# Microcontroller.net
KiCad netlist of a schematic drawn in Altium Designer
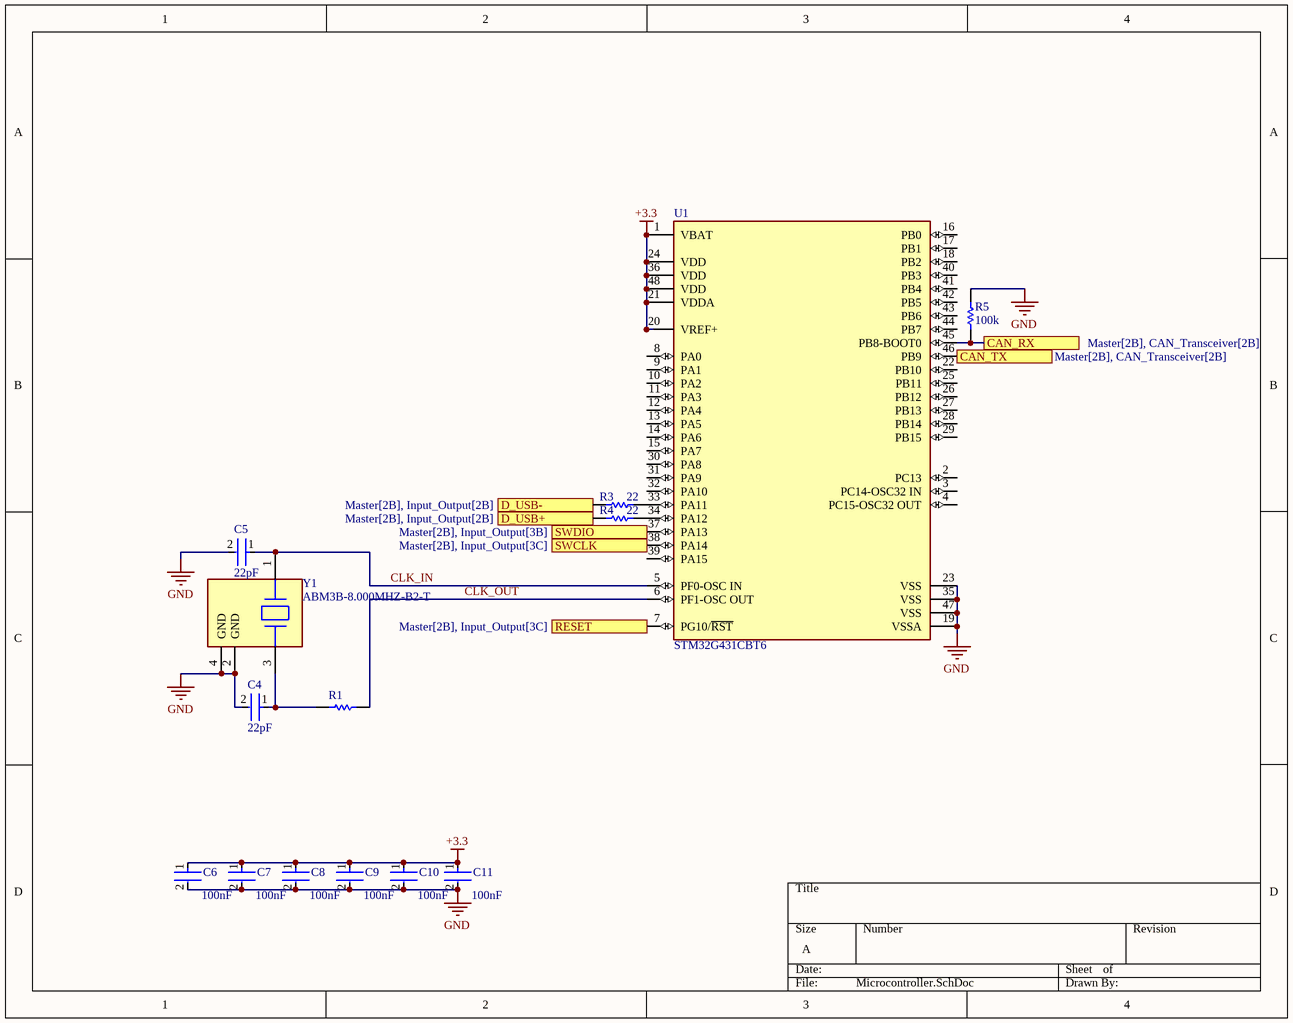
[diagram p0: Microcontroller.SchDoc]

(export (version "E")
  (design (tool "Eeschema 10.0.6"))
  (components
    (comp (ref "C4")
      (value "22pF")
      (footprint "CAPC0603(1608)100_L")
      (description "GENERIC CAPACITOR 0805 or 0603(1608)")
      (libsource (lib "Sooner Competitive Robotics") (part "11868f565c42a9108669ba33697ecf6"))
    )
    (comp (ref "C5")
      (value "22pF")
      (footprint "CAPC0603(1608)100_L")
      (description "GENERIC CAPACITOR 0805 or 0603(1608)")
      (libsource (lib "Sooner Competitive Robotics") (part "11868f565c42a9108669ba33697ecf6"))
    )
    (comp (ref "C6")
      (value "100nF")
      (footprint "CAPC0603(1608)100_L")
      (description "GENERIC CAPACITOR 0805 or 0603(1608)")
      (libsource (lib "Sooner Competitive Robotics") (part "11868f565c42a9108669ba33697ecf6"))
    )
    (comp (ref "C7")
      (value "100nF")
      (footprint "CAPC0603(1608)100_L")
      (description "GENERIC CAPACITOR 0805 or 0603(1608)")
      (libsource (lib "Sooner Competitive Robotics") (part "11868f565c42a9108669ba33697ecf6"))
    )
    (comp (ref "C8")
      (value "100nF")
      (footprint "CAPC0603(1608)100_L")
      (description "GENERIC CAPACITOR 0805 or 0603(1608)")
      (libsource (lib "Sooner Competitive Robotics") (part "11868f565c42a9108669ba33697ecf6"))
    )
    (comp (ref "C9")
      (value "100nF")
      (footprint "CAPC0603(1608)100_L")
      (description "GENERIC CAPACITOR 0805 or 0603(1608)")
      (libsource (lib "Sooner Competitive Robotics") (part "11868f565c42a9108669ba33697ecf6"))
    )
    (comp (ref "C10")
      (value "100nF")
      (footprint "CAPC0603(1608)100_L")
      (description "GENERIC CAPACITOR 0805 or 0603(1608)")
      (libsource (lib "Sooner Competitive Robotics") (part "11868f565c42a9108669ba33697ecf6"))
    )
    (comp (ref "C11")
      (value "100nF")
      (footprint "CAPC0603(1608)100_L")
      (description "GENERIC CAPACITOR 0805 or 0603(1608)")
      (libsource (lib "Sooner Competitive Robotics") (part "11868f565c42a9108669ba33697ecf6"))
    )
    (comp (ref "R1")
      (value "RES 0805")
      (footprint "RESC2013X50X30ML20T20")
      (description "Surface Mount 0805 Resistor")
      (libsource (lib "Sooner Competitive Robotics") (part "RES"))
    )
    (comp (ref "R3")
      (value "22")
      (footprint "RESC2013X50X30ML20T20")
      (description "Surface Mount 0805 Resistor")
      (libsource (lib "Sooner Competitive Robotics") (part "RES"))
    )
    (comp (ref "R4")
      (value "22")
      (footprint "RESC2013X50X30ML20T20")
      (description "Surface Mount 0805 Resistor")
      (libsource (lib "Sooner Competitive Robotics") (part "RES"))
    )
    (comp (ref "R5")
      (value "100k")
      (footprint "RESC2013X50X30ML20T20")
      (description "Surface Mount 0805 Resistor")
      (libsource (lib "Sooner Competitive Robotics") (part "RES"))
    )
    (comp (ref "U1")
      (value "STM32G431CBT6")
      (footprint "FP-LQFP48-5B-MFG")
      (description "MAINSTREAM ARM CORTEX-M4+ MCU 17")
      (fields
        (field (name "MANUFACTURER") "STMicroelectronics")
        (field (name "OCTOPART") "https://octopart.com/stm32g431cbt6-stmicroelectronics-98835224")
      )
      (libsource (lib "Altium Content Vault") (part "08b09c1d51ec08ade740842f2b8671b"))
    )
    (comp (ref "Y1")
      (value "ABM3B-8.000MHZ-B2-T")
      (footprint "FP-ABM3B-MFG")
      (description "Crystal 8MHz ±20ppm 18pF SMD-4 5mm x 3.2mm")
      (fields (field (name "TOLERANCE") "20ppm"))
      (libsource (lib "Altium Content Vault") (part "48e526d86b7f2615d98721063c72f49"))
    )
  )
  (nets
    (net (code "1") (name "+3.3") (class "Default")
      (node (ref "C10") (pin "1") (pinfunction "1_1") (pintype "passive"))
      (node (ref "C11") (pin "1") (pinfunction "1_1") (pintype "passive"))
      (node (ref "C6") (pin "1") (pinfunction "1_1") (pintype "passive"))
      (node (ref "C7") (pin "1") (pinfunction "1_1") (pintype "passive"))
      (node (ref "C8") (pin "1") (pinfunction "1_1") (pintype "passive"))
      (node (ref "C9") (pin "1") (pinfunction "1_1") (pintype "passive"))
      (node (ref "U1") (pin "1") (pinfunction "VBAT_1") (pintype "power_in"))
      (node (ref "U1") (pin "20") (pinfunction "VREF+_20") (pintype "power_in"))
      (node (ref "U1") (pin "21") (pinfunction "VDDA_21") (pintype "power_in"))
      (node (ref "U1") (pin "24") (pinfunction "VDD_24") (pintype "power_in"))
      (node (ref "U1") (pin "36") (pinfunction "VDD_36") (pintype "power_in"))
      (node (ref "U1") (pin "48") (pinfunction "VDD_48") (pintype "power_in"))
    )
    (net (code "2") (name "/CAN_RX") (class "Default")
      (node (ref "R5") (pin "1") (pinfunction "1_1") (pintype "passive"))
      (node (ref "U1") (pin "45") (pinfunction "PB8-BOOT0_45") (pintype "bidirectional"))
    )
    (net (code "3") (name "/CAN_TX") (class "Default")
      (node (ref "U1") (pin "46") (pinfunction "PB9_46") (pintype "bidirectional"))
    )
    (net (code "4") (name "/CLK_IN") (class "Default")
      (node (ref "C5") (pin "1") (pinfunction "1_1") (pintype "passive"))
      (node (ref "U1") (pin "5") (pinfunction "PF0-OSC_IN_5") (pintype "bidirectional"))
      (node (ref "Y1") (pin "1") (pinfunction "1_1") (pintype "passive"))
    )
    (net (code "5") (name "/CLK_OUT") (class "Default")
      (node (ref "R1") (pin "2") (pinfunction "2_2") (pintype "passive"))
      (node (ref "U1") (pin "6") (pinfunction "PF1-OSC_OUT_6") (pintype "bidirectional"))
    )
    (net (code "6") (name "/D_USB+") (class "Default")
      (node (ref "R4") (pin "1") (pinfunction "1_1") (pintype "passive"))
    )
    (net (code "7") (name "/D_USB-") (class "Default")
      (node (ref "R3") (pin "1") (pinfunction "1_1") (pintype "passive"))
    )
    (net (code "8") (name "/RESET") (class "Default")
      (node (ref "U1") (pin "7") (pinfunction "PG10/~{RST}_7") (pintype "bidirectional"))
    )
    (net (code "9") (name "/SWCLK") (class "Default")
      (node (ref "U1") (pin "38") (pinfunction "PA14_38") (pintype "bidirectional"))
    )
    (net (code "10") (name "/SWDIO") (class "Default")
      (node (ref "U1") (pin "37") (pinfunction "PA13_37") (pintype "bidirectional"))
    )
    (net (code "11") (name "GND") (class "Default")
      (node (ref "C10") (pin "2") (pinfunction "2_2") (pintype "passive"))
      (node (ref "C11") (pin "2") (pinfunction "2_2") (pintype "passive"))
      (node (ref "C4") (pin "2") (pinfunction "2_2") (pintype "passive"))
      (node (ref "C5") (pin "2") (pinfunction "2_2") (pintype "passive"))
      (node (ref "C6") (pin "2") (pinfunction "2_2") (pintype "passive"))
      (node (ref "C7") (pin "2") (pinfunction "2_2") (pintype "passive"))
      (node (ref "C8") (pin "2") (pinfunction "2_2") (pintype "passive"))
      (node (ref "C9") (pin "2") (pinfunction "2_2") (pintype "passive"))
      (node (ref "R5") (pin "2") (pinfunction "2_2") (pintype "passive"))
      (node (ref "U1") (pin "19") (pinfunction "VSSA_19") (pintype "power_in"))
      (node (ref "U1") (pin "23") (pinfunction "VSS_23") (pintype "power_in"))
      (node (ref "U1") (pin "35") (pinfunction "VSS_35") (pintype "power_in"))
      (node (ref "U1") (pin "47") (pinfunction "VSS_47") (pintype "power_in"))
      (node (ref "Y1") (pin "2") (pinfunction "GND_2") (pintype "power_in"))
      (node (ref "Y1") (pin "4") (pinfunction "GND_4") (pintype "power_in"))
    )
    (net (code "12") (name "Net-(C4-Pad1)") (class "Default")
      (node (ref "C4") (pin "1") (pinfunction "1_1") (pintype "passive"))
      (node (ref "R1") (pin "1") (pinfunction "1_1") (pintype "passive"))
      (node (ref "Y1") (pin "3") (pinfunction "3_3") (pintype "passive"))
    )
    (net (code "13") (name "Net-(U1-PA11)") (class "Default")
      (node (ref "R3") (pin "2") (pinfunction "2_2") (pintype "passive"))
      (node (ref "U1") (pin "33") (pinfunction "PA11_33") (pintype "bidirectional"))
    )
    (net (code "14") (name "Net-(U1-PA12)") (class "Default")
      (node (ref "R4") (pin "2") (pinfunction "2_2") (pintype "passive"))
      (node (ref "U1") (pin "34") (pinfunction "PA12_34") (pintype "bidirectional"))
    )
    (net (code "15") (name "unconnected-(U1-PA0-Pad8)") (class "Default")
      (node (ref "U1") (pin "8") (pinfunction "PA0_8") (pintype "bidirectional"))
    )
    (net (code "16") (name "unconnected-(U1-PA1-Pad9)") (class "Default")
      (node (ref "U1") (pin "9") (pinfunction "PA1_9") (pintype "bidirectional"))
    )
    (net (code "17") (name "unconnected-(U1-PA2-Pad10)") (class "Default")
      (node (ref "U1") (pin "10") (pinfunction "PA2_10") (pintype "bidirectional"))
    )
    (net (code "18") (name "unconnected-(U1-PA3-Pad11)") (class "Default")
      (node (ref "U1") (pin "11") (pinfunction "PA3_11") (pintype "bidirectional"))
    )
    (net (code "19") (name "unconnected-(U1-PA4-Pad12)") (class "Default")
      (node (ref "U1") (pin "12") (pinfunction "PA4_12") (pintype "bidirectional"))
    )
    (net (code "20") (name "unconnected-(U1-PA5-Pad13)") (class "Default")
      (node (ref "U1") (pin "13") (pinfunction "PA5_13") (pintype "bidirectional"))
    )
    (net (code "21") (name "unconnected-(U1-PA6-Pad14)") (class "Default")
      (node (ref "U1") (pin "14") (pinfunction "PA6_14") (pintype "bidirectional"))
    )
    (net (code "22") (name "unconnected-(U1-PA7-Pad15)") (class "Default")
      (node (ref "U1") (pin "15") (pinfunction "PA7_15") (pintype "bidirectional"))
    )
    (net (code "23") (name "unconnected-(U1-PA8-Pad30)") (class "Default")
      (node (ref "U1") (pin "30") (pinfunction "PA8_30") (pintype "bidirectional"))
    )
    (net (code "24") (name "unconnected-(U1-PA9-Pad31)") (class "Default")
      (node (ref "U1") (pin "31") (pinfunction "PA9_31") (pintype "bidirectional"))
    )
    (net (code "25") (name "unconnected-(U1-PA10-Pad32)") (class "Default")
      (node (ref "U1") (pin "32") (pinfunction "PA10_32") (pintype "bidirectional"))
    )
    (net (code "26") (name "unconnected-(U1-PA15-Pad39)") (class "Default")
      (node (ref "U1") (pin "39") (pinfunction "PA15_39") (pintype "bidirectional"))
    )
    (net (code "27") (name "unconnected-(U1-PB0-Pad16)") (class "Default")
      (node (ref "U1") (pin "16") (pinfunction "PB0_16") (pintype "bidirectional"))
    )
    (net (code "28") (name "unconnected-(U1-PB1-Pad17)") (class "Default")
      (node (ref "U1") (pin "17") (pinfunction "PB1_17") (pintype "bidirectional"))
    )
    (net (code "29") (name "unconnected-(U1-PB2-Pad18)") (class "Default")
      (node (ref "U1") (pin "18") (pinfunction "PB2_18") (pintype "bidirectional"))
    )
    (net (code "30") (name "unconnected-(U1-PB3-Pad40)") (class "Default")
      (node (ref "U1") (pin "40") (pinfunction "PB3_40") (pintype "bidirectional"))
    )
    (net (code "31") (name "unconnected-(U1-PB4-Pad41)") (class "Default")
      (node (ref "U1") (pin "41") (pinfunction "PB4_41") (pintype "bidirectional"))
    )
    (net (code "32") (name "unconnected-(U1-PB5-Pad42)") (class "Default")
      (node (ref "U1") (pin "42") (pinfunction "PB5_42") (pintype "bidirectional"))
    )
    (net (code "33") (name "unconnected-(U1-PB6-Pad43)") (class "Default")
      (node (ref "U1") (pin "43") (pinfunction "PB6_43") (pintype "bidirectional"))
    )
    (net (code "34") (name "unconnected-(U1-PB7-Pad44)") (class "Default")
      (node (ref "U1") (pin "44") (pinfunction "PB7_44") (pintype "bidirectional"))
    )
    (net (code "35") (name "unconnected-(U1-PB10-Pad22)") (class "Default")
      (node (ref "U1") (pin "22") (pinfunction "PB10_22") (pintype "bidirectional"))
    )
    (net (code "36") (name "unconnected-(U1-PB11-Pad25)") (class "Default")
      (node (ref "U1") (pin "25") (pinfunction "PB11_25") (pintype "bidirectional"))
    )
    (net (code "37") (name "unconnected-(U1-PB12-Pad26)") (class "Default")
      (node (ref "U1") (pin "26") (pinfunction "PB12_26") (pintype "bidirectional"))
    )
    (net (code "38") (name "unconnected-(U1-PB13-Pad27)") (class "Default")
      (node (ref "U1") (pin "27") (pinfunction "PB13_27") (pintype "bidirectional"))
    )
    (net (code "39") (name "unconnected-(U1-PB14-Pad28)") (class "Default")
      (node (ref "U1") (pin "28") (pinfunction "PB14_28") (pintype "bidirectional"))
    )
    (net (code "40") (name "unconnected-(U1-PB15-Pad29)") (class "Default")
      (node (ref "U1") (pin "29") (pinfunction "PB15_29") (pintype "bidirectional"))
    )
    (net (code "41") (name "unconnected-(U1-PC13-Pad2)") (class "Default")
      (node (ref "U1") (pin "2") (pinfunction "PC13_2") (pintype "bidirectional"))
    )
    (net (code "42") (name "unconnected-(U1-PC14-OSC32_IN-Pad3)") (class "Default")
      (node (ref "U1") (pin "3") (pinfunction "PC14-OSC32_IN_3") (pintype "bidirectional"))
    )
    (net (code "43") (name "unconnected-(U1-PC15-OSC32_OUT-Pad4)") (class "Default")
      (node (ref "U1") (pin "4") (pinfunction "PC15-OSC32_OUT_4") (pintype "bidirectional"))
    )
  )
)
